# battery-led.net
KiCad netlist of a schematic drawn in Altium Designer
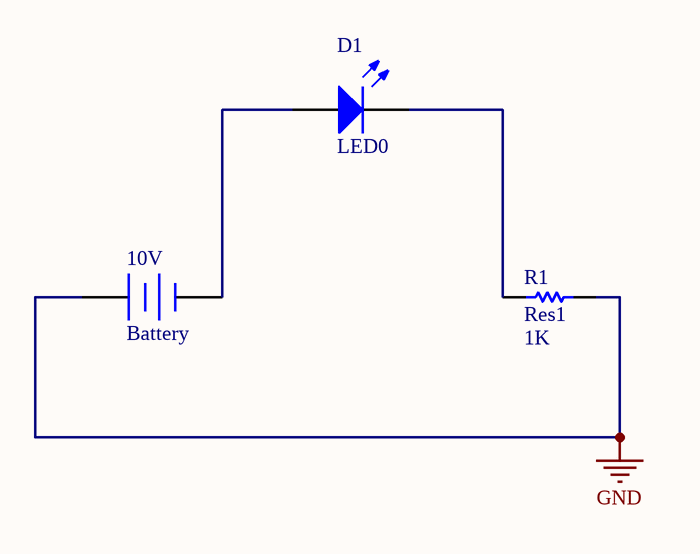
[diagram p0: battery-led.SchDoc]

(export (version "E")
  (design (tool "Eeschema 10.0.6"))
  (components
    (comp (ref "10V")
      (value "Battery")
      (footprint "BAT-2")
      (description "Multicell Battery")
      (fields (field (name "PUBLISHER") "Altium Limited"))
      (libsource (lib "Miscellaneous Devices") (part "Battery"))
    )
    (comp (ref "D1")
      (value "LED0")
      (footprint "LED-0")
      (description "Typical INFRARED GaAs LED")
      (fields (field (name "PUBLISHER") "Altium Limited"))
      (libsource (lib "Miscellaneous Devices") (part "LED0"))
    )
    (comp (ref "R1")
      (value "Res1")
      (footprint "AXIAL-0.3")
      (description "Resistor")
      (fields (field (name "ALTIUM_VALUE") "1K") (field (name "PUBLISHER") "Altium Limited"))
      (libsource (lib "Miscellaneous Devices") (part "Res1"))
    )
  )
  (nets
    (net (code "1") (name "GND") (class "Default")
      (node (ref "10V") (pin "1") (pinfunction "+_1") (pintype "passive"))
      (node (ref "R1") (pin "2") (pinfunction "2_2") (pintype "passive"))
    )
    (net (code "2") (name "Net-(10V--)") (class "Default")
      (node (ref "10V") (pin "2") (pinfunction "-_2") (pintype "passive"))
      (node (ref "D1") (pin "1") (pinfunction "A_1") (pintype "passive"))
    )
    (net (code "3") (name "Net-(D1-K)") (class "Default")
      (node (ref "D1") (pin "2") (pinfunction "K_2") (pintype "passive"))
      (node (ref "R1") (pin "1") (pinfunction "1_1") (pintype "passive"))
    )
  )
)
